# ProPrj__-__2025-12-05.net
KiCad netlist of a schematic drawn in EasyEDA Pro
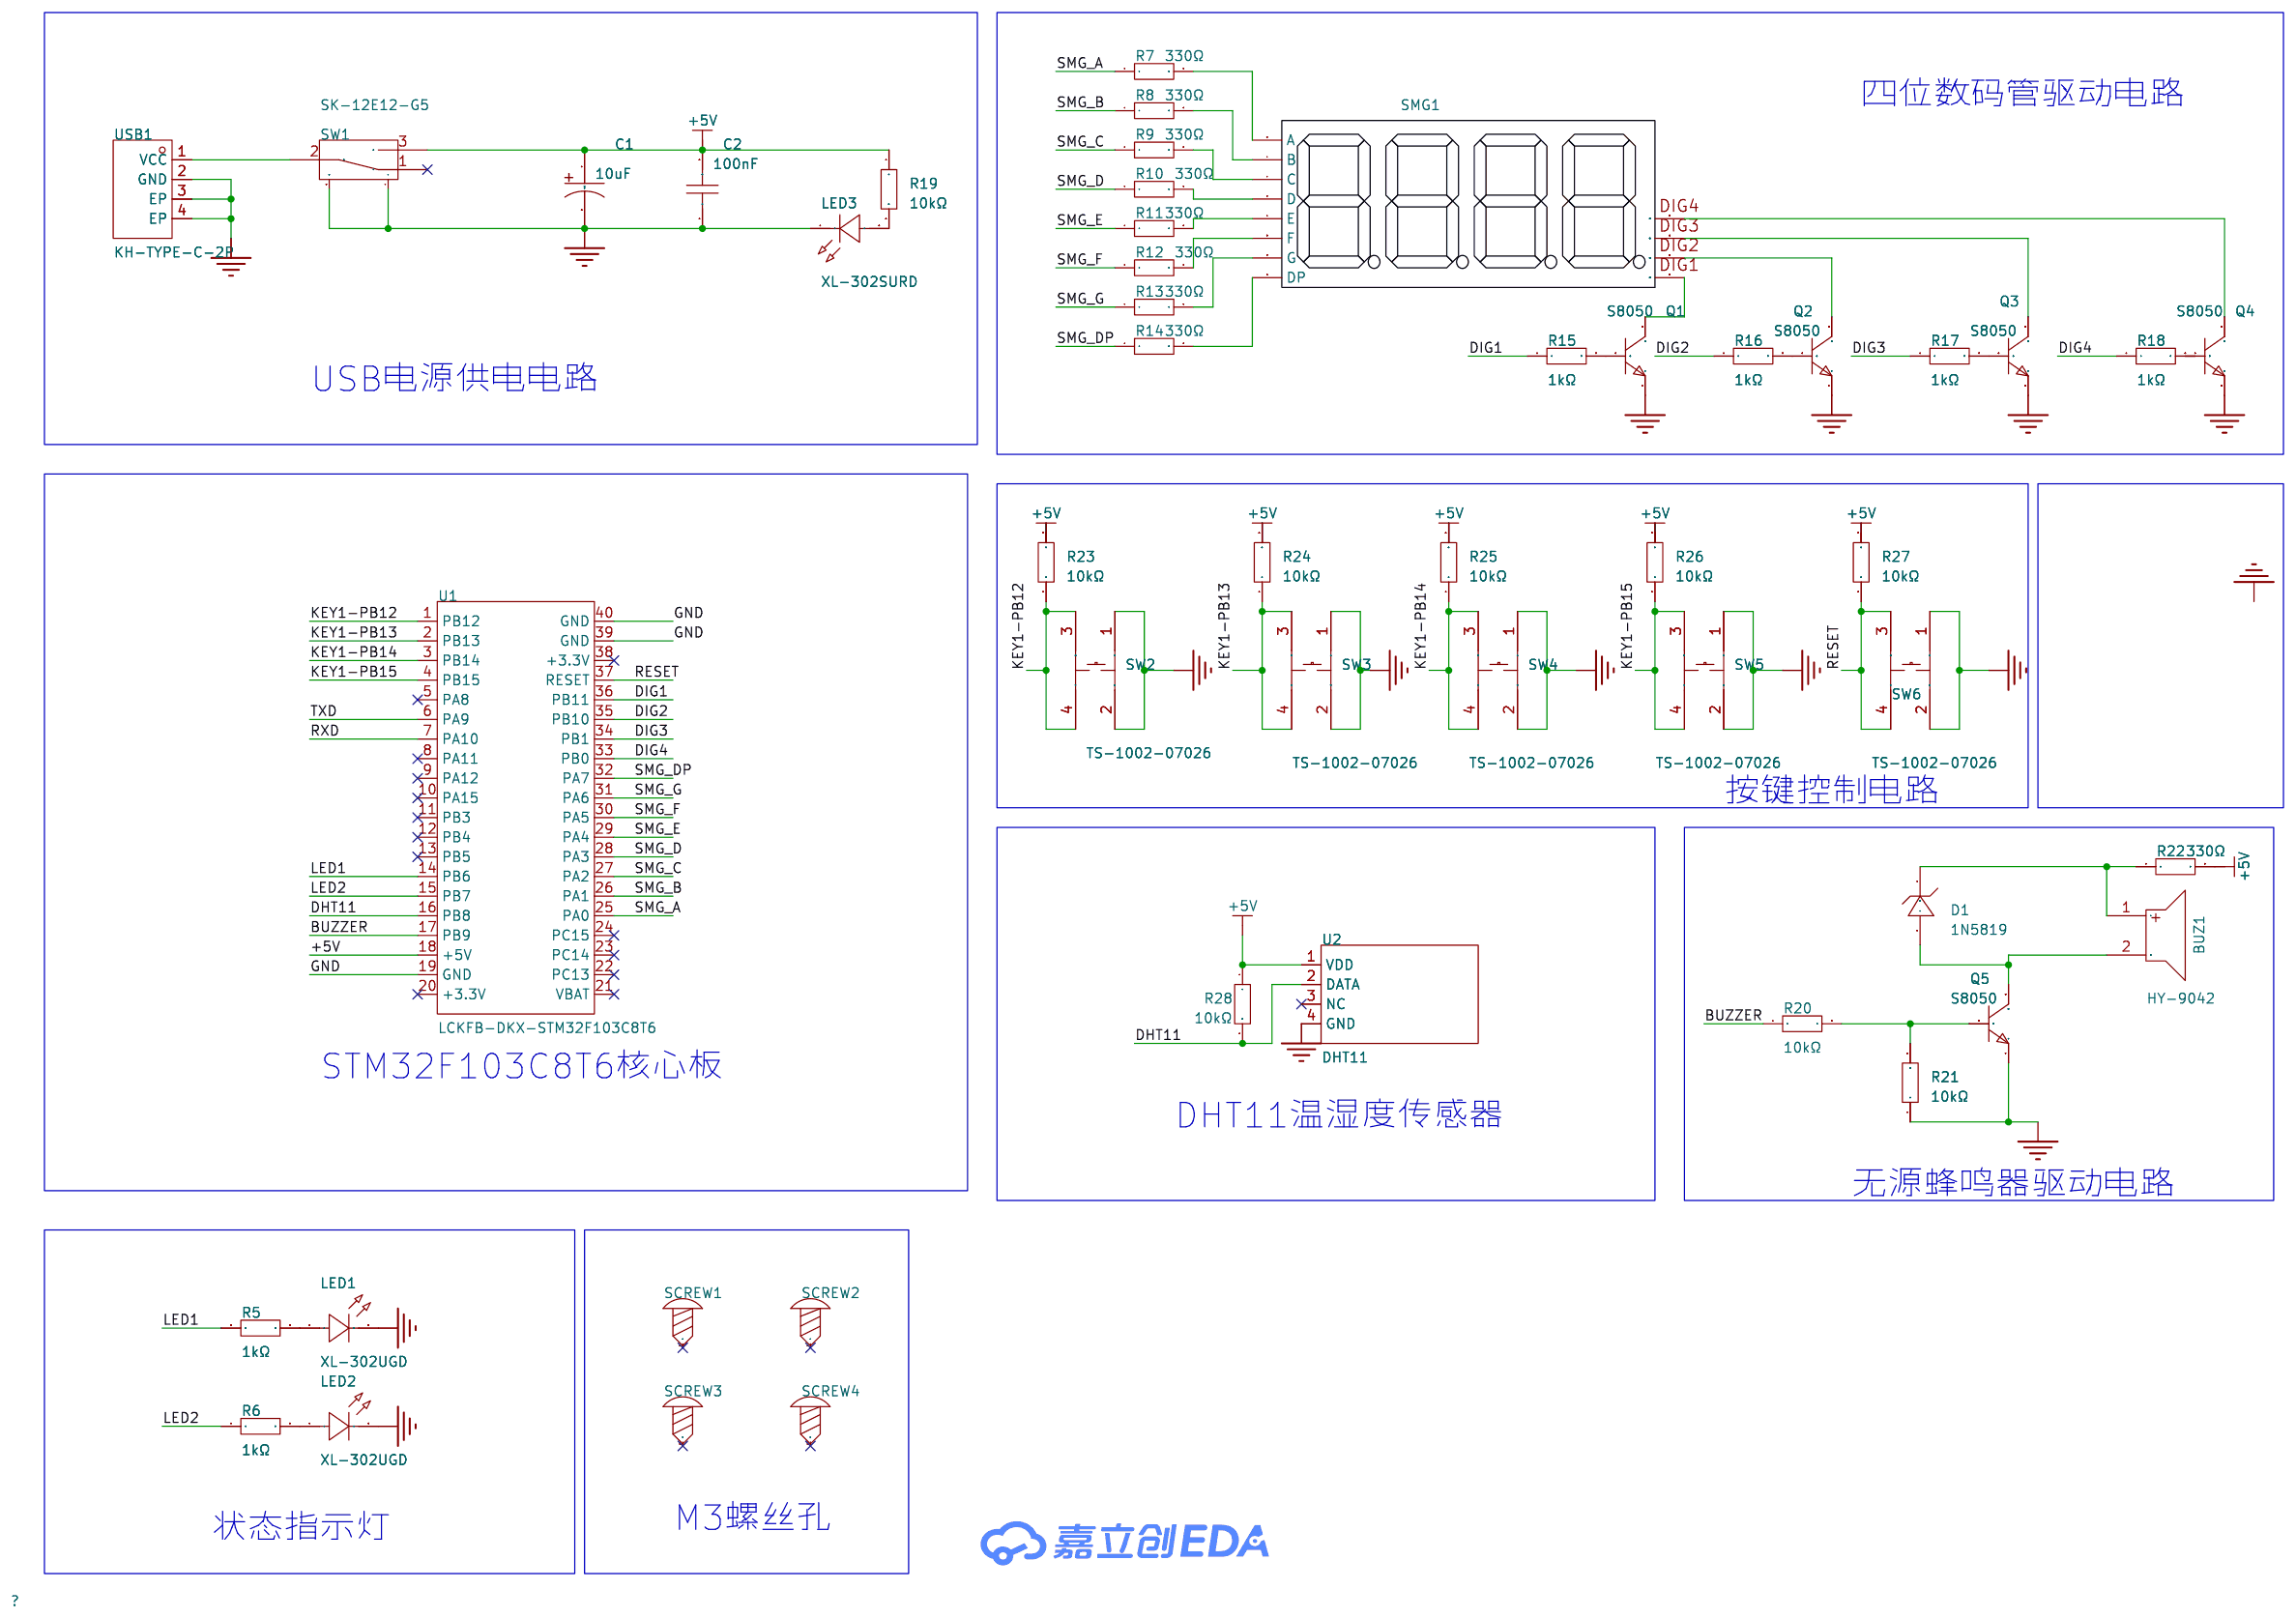
[diagram p0: schematic sheet]

(export (version "E")
  (design (tool "Eeschema 10.0.6"))
  (components
    (comp (ref "BUZ1")
      (value "HY-9042")
      (footprint "easyedapro:BUZ-TH_BD9.0-P4.00-D0.6-FD")
      (libsource (lib "easyedapro") (part "HY-9042"))
    )
    (comp (ref "C1")
      (value "10uF")
      (footprint "easyedapro:CAP-TH_BD4.0-P1.50-D0.8-FD")
      (description "容值:10uF;精度:±20%;额定电压:25V;")
      (fields
        (field (name "Manufacturer Part") "KF1E100MB050A00CV0")
        (field (name "Manufacturer") "HUAWEI(华威集团)")
      )
      (libsource (lib "easyedapro") (part "KF1E100MB050A00CV0"))
    )
    (comp (ref "C2")
      (value "100nF")
      (footprint "easyedapro:CAP-TH_L5.0-W2.5-P5.08-D0.7")
      (description "容值:100nF;精度:-20%~+80%;额定电压:50V;温度系数:Y5V;")
      (fields
        (field (name "Manufacturer Part") "CC1H104ZC74D3F5O30MN")
        (field (name "Manufacturer") "Dersonic(德尔创)")
      )
      (libsource (lib "easyedapro") (part "CC1H104ZC74D3F5O30MN"))
    )
    (comp (ref "D1")
      (value "1N5819")
      (footprint "easyedapro:DO-41_BD2.4-L4.7-P8.70-D0.9-RD")
      (description "二极管配置:独立式;正向压降(Vf):900mV@3A;直流反向耐压(Vr):40V;整流电流:1A;")
      (fields (field (name "Manufacturer") "LGE(鲁光)"))
      (libsource (lib "easyedapro") (part "1N5819_C402218"))
    )
    (comp (ref "LED1")
      (value "XL-302UGD")
      (footprint "easyedapro:LED-TH_BD3.8-P2.54-FD_GREEN")
      (fields (field (name "Manufacturer") "XINGLIGHT(成兴光)"))
      (libsource (lib "easyedapro") (part "XL-302UGD"))
    )
    (comp (ref "LED2")
      (value "XL-302UGD")
      (footprint "easyedapro:LED-TH_BD3.8-P2.54-FD_GREEN")
      (fields (field (name "Manufacturer") "XINGLIGHT(成兴光)"))
      (libsource (lib "easyedapro") (part "XL-302UGD"))
    )
    (comp (ref "LED3")
      (value "XL-302SURD")
      (footprint "easyedapro:LED-TH_BD3.8-P2.54-RD")
      (fields (field (name "Manufacturer") "XINGLIGHT(成兴光)"))
      (libsource (lib "easyedapro") (part "XL-302SURD"))
    )
    (comp (ref "Q1")
      (value "S8050")
      (footprint "easyedapro:TO-92-3_L4.5-W3.5-P1.27-L")
      (description "晶体管类型:NPN;集电极电流(Ic):500mA;集射极击穿电压(Vceo):25V;耗散功率(Pd):625mW;直流电流增益(hFE):160@50mA,1V;")
      (fields (field (name "Manufacturer") "JSMSEMI(杰盛微)"))
      (libsource (lib "easyedapro") (part "S8050_C2931492"))
    )
    (comp (ref "Q2")
      (value "S8050")
      (footprint "easyedapro:TO-92-3_L4.5-W3.5-P1.27-L")
      (description "晶体管类型:NPN;集电极电流(Ic):500mA;集射极击穿电压(Vceo):25V;耗散功率(Pd):625mW;直流电流增益(hFE):160@50mA,1V;")
      (fields (field (name "Manufacturer") "JSMSEMI(杰盛微)"))
      (libsource (lib "easyedapro") (part "S8050_C2931492"))
    )
    (comp (ref "Q3")
      (value "S8050")
      (footprint "easyedapro:TO-92-3_L4.5-W3.5-P1.27-L")
      (description "晶体管类型:NPN;集电极电流(Ic):500mA;集射极击穿电压(Vceo):25V;耗散功率(Pd):625mW;直流电流增益(hFE):160@50mA,1V;")
      (fields (field (name "Manufacturer") "JSMSEMI(杰盛微)"))
      (libsource (lib "easyedapro") (part "S8050_C2931492"))
    )
    (comp (ref "Q4")
      (value "S8050")
      (footprint "easyedapro:TO-92-3_L4.5-W3.5-P1.27-L")
      (description "晶体管类型:NPN;集电极电流(Ic):500mA;集射极击穿电压(Vceo):25V;耗散功率(Pd):625mW;直流电流增益(hFE):160@50mA,1V;")
      (fields (field (name "Manufacturer") "JSMSEMI(杰盛微)"))
      (libsource (lib "easyedapro") (part "S8050_C2931492"))
    )
    (comp (ref "Q5")
      (value "S8050")
      (footprint "easyedapro:TO-92-3_L4.5-W3.5-P1.27-L")
      (description "晶体管类型:NPN;集电极电流(Ic):500mA;集射极击穿电压(Vceo):25V;耗散功率(Pd):625mW;直流电流增益(hFE):160@50mA,1V;")
      (fields (field (name "Manufacturer") "JSMSEMI(杰盛微)"))
      (libsource (lib "easyedapro") (part "S8050_C2931492"))
    )
    (comp (ref "R5")
      (value "1kΩ")
      (footprint "easyedapro:RES-TH_BD2.2-L6.5-P10.50-D0.6")
      (description "电阻类型:金属膜电阻;阻值:1kΩ;精度:±5%;功率:250mW;")
      (fields (field (name "Manufacturer Part") "MFR-25JT-52-1K") (field (name "Manufacturer") "YAGEO(国巨)"))
      (libsource (lib "easyedapro") (part "MFR-25JT-52-1K"))
    )
    (comp (ref "R6")
      (value "1kΩ")
      (footprint "easyedapro:RES-TH_BD2.2-L6.5-P10.50-D0.6")
      (description "电阻类型:金属膜电阻;阻值:1kΩ;精度:±5%;功率:250mW;")
      (fields (field (name "Manufacturer Part") "MFR-25JT-52-1K") (field (name "Manufacturer") "YAGEO(国巨)"))
      (libsource (lib "easyedapro") (part "MFR-25JT-52-1K"))
    )
    (comp (ref "R7")
      (value "330Ω")
      (footprint "easyedapro:RES-TH_BD2.2-L6.5-P10.50-D0.6")
      (description "电阻类型:金属膜电阻;阻值:330Ω;精度:±1%;功率:250mW;温度系数:±50ppm/°C;")
      (fields (field (name "Manufacturer Part") "MFR-25FTE52-330R") (field (name "Manufacturer") "YAGEO(国巨)"))
      (libsource (lib "easyedapro") (part "MFR-25FTE52-330R"))
    )
    (comp (ref "R8")
      (value "330Ω")
      (footprint "easyedapro:RES-TH_BD2.2-L6.5-P10.50-D0.6")
      (description "电阻类型:金属膜电阻;阻值:330Ω;精度:±1%;功率:250mW;温度系数:±50ppm/°C;")
      (fields (field (name "Manufacturer Part") "MFR-25FTE52-330R") (field (name "Manufacturer") "YAGEO(国巨)"))
      (libsource (lib "easyedapro") (part "MFR-25FTE52-330R"))
    )
    (comp (ref "R9")
      (value "330Ω")
      (footprint "easyedapro:RES-TH_BD2.2-L6.5-P10.50-D0.6")
      (description "电阻类型:金属膜电阻;阻值:330Ω;精度:±1%;功率:250mW;温度系数:±50ppm/°C;")
      (fields (field (name "Manufacturer Part") "MFR-25FTE52-330R") (field (name "Manufacturer") "YAGEO(国巨)"))
      (libsource (lib "easyedapro") (part "MFR-25FTE52-330R"))
    )
    (comp (ref "R10")
      (value "330Ω")
      (footprint "easyedapro:RES-TH_BD2.2-L6.5-P10.50-D0.6")
      (description "电阻类型:金属膜电阻;阻值:330Ω;精度:±1%;功率:250mW;温度系数:±50ppm/°C;")
      (fields (field (name "Manufacturer Part") "MFR-25FTE52-330R") (field (name "Manufacturer") "YAGEO(国巨)"))
      (libsource (lib "easyedapro") (part "MFR-25FTE52-330R"))
    )
    (comp (ref "R11")
      (value "330Ω")
      (footprint "easyedapro:RES-TH_BD2.2-L6.5-P10.50-D0.6")
      (description "电阻类型:金属膜电阻;阻值:330Ω;精度:±1%;功率:250mW;温度系数:±50ppm/°C;")
      (fields (field (name "Manufacturer Part") "MFR-25FTE52-330R") (field (name "Manufacturer") "YAGEO(国巨)"))
      (libsource (lib "easyedapro") (part "MFR-25FTE52-330R"))
    )
    (comp (ref "R12")
      (value "330Ω")
      (footprint "easyedapro:RES-TH_BD2.2-L6.5-P10.50-D0.6")
      (description "电阻类型:金属膜电阻;阻值:330Ω;精度:±1%;功率:250mW;温度系数:±50ppm/°C;")
      (fields (field (name "Manufacturer Part") "MFR-25FTE52-330R") (field (name "Manufacturer") "YAGEO(国巨)"))
      (libsource (lib "easyedapro") (part "MFR-25FTE52-330R"))
    )
    (comp (ref "R13")
      (value "330Ω")
      (footprint "easyedapro:RES-TH_BD2.2-L6.5-P10.50-D0.6")
      (description "电阻类型:金属膜电阻;阻值:330Ω;精度:±1%;功率:250mW;温度系数:±50ppm/°C;")
      (fields (field (name "Manufacturer Part") "MFR-25FTE52-330R") (field (name "Manufacturer") "YAGEO(国巨)"))
      (libsource (lib "easyedapro") (part "MFR-25FTE52-330R"))
    )
    (comp (ref "R14")
      (value "330Ω")
      (footprint "easyedapro:RES-TH_BD2.2-L6.5-P10.50-D0.6")
      (description "电阻类型:金属膜电阻;阻值:330Ω;精度:±1%;功率:250mW;温度系数:±50ppm/°C;")
      (fields (field (name "Manufacturer Part") "MFR-25FTE52-330R") (field (name "Manufacturer") "YAGEO(国巨)"))
      (libsource (lib "easyedapro") (part "MFR-25FTE52-330R"))
    )
    (comp (ref "R15")
      (value "1kΩ")
      (footprint "easyedapro:RES-TH_BD2.2-L6.5-P10.50-D0.6")
      (description "电阻类型:金属膜电阻;阻值:1kΩ;精度:±5%;功率:250mW;")
      (fields (field (name "Manufacturer Part") "MFR-25JT-52-1K") (field (name "Manufacturer") "YAGEO(国巨)"))
      (libsource (lib "easyedapro") (part "MFR-25JT-52-1K"))
    )
    (comp (ref "R16")
      (value "1kΩ")
      (footprint "easyedapro:RES-TH_BD2.2-L6.5-P10.50-D0.6")
      (description "电阻类型:金属膜电阻;阻值:1kΩ;精度:±5%;功率:250mW;")
      (fields (field (name "Manufacturer Part") "MFR-25JT-52-1K") (field (name "Manufacturer") "YAGEO(国巨)"))
      (libsource (lib "easyedapro") (part "MFR-25JT-52-1K"))
    )
    (comp (ref "R17")
      (value "1kΩ")
      (footprint "easyedapro:RES-TH_BD2.2-L6.5-P10.50-D0.6")
      (description "电阻类型:金属膜电阻;阻值:1kΩ;精度:±5%;功率:250mW;")
      (fields (field (name "Manufacturer Part") "MFR-25JT-52-1K") (field (name "Manufacturer") "YAGEO(国巨)"))
      (libsource (lib "easyedapro") (part "MFR-25JT-52-1K"))
    )
    (comp (ref "R18")
      (value "1kΩ")
      (footprint "easyedapro:RES-TH_BD2.2-L6.5-P10.50-D0.6")
      (description "电阻类型:金属膜电阻;阻值:1kΩ;精度:±5%;功率:250mW;")
      (fields (field (name "Manufacturer Part") "MFR-25JT-52-1K") (field (name "Manufacturer") "YAGEO(国巨)"))
      (libsource (lib "easyedapro") (part "MFR-25JT-52-1K"))
    )
    (comp (ref "R19")
      (value "10kΩ")
      (footprint "easyedapro:RES-TH_BD2.4-L6.3-P10.30-D0.6")
      (description "电阻类型:金属膜电阻;阻值:10kΩ;精度:±5%;功率:250mW;")
      (fields (field (name "Manufacturer Part") "MFR-25JT-52-10K") (field (name "Manufacturer") "YAGEO(国巨)"))
      (libsource (lib "easyedapro") (part "MFR-25JT-52-10K"))
    )
    (comp (ref "R20")
      (value "10kΩ")
      (footprint "easyedapro:RES-TH_BD2.4-L6.3-P10.30-D0.6")
      (description "电阻类型:金属膜电阻;阻值:10kΩ;精度:±5%;功率:250mW;")
      (fields (field (name "Manufacturer Part") "MFR-25JT-52-10K") (field (name "Manufacturer") "YAGEO(国巨)"))
      (libsource (lib "easyedapro") (part "MFR-25JT-52-10K"))
    )
    (comp (ref "R21")
      (value "10kΩ")
      (footprint "easyedapro:RES-TH_BD2.4-L6.3-P10.30-D0.6")
      (description "电阻类型:金属膜电阻;阻值:10kΩ;精度:±5%;功率:250mW;")
      (fields (field (name "Manufacturer Part") "MFR-25JT-52-10K") (field (name "Manufacturer") "YAGEO(国巨)"))
      (libsource (lib "easyedapro") (part "MFR-25JT-52-10K"))
    )
    (comp (ref "R22")
      (value "330Ω")
      (footprint "easyedapro:RES-TH_BD2.2-L6.5-P10.50-D0.6")
      (description "电阻类型:金属膜电阻;阻值:330Ω;精度:±1%;功率:250mW;温度系数:±50ppm/°C;")
      (fields (field (name "Manufacturer Part") "MFR-25FTE52-330R") (field (name "Manufacturer") "YAGEO(国巨)"))
      (libsource (lib "easyedapro") (part "MFR-25FTE52-330R"))
    )
    (comp (ref "R23")
      (value "10kΩ")
      (footprint "easyedapro:RES-TH_BD2.4-L6.3-P10.30-D0.6")
      (description "电阻类型:金属膜电阻;阻值:10kΩ;精度:±5%;功率:250mW;")
      (fields (field (name "Manufacturer Part") "MFR-25JT-52-10K") (field (name "Manufacturer") "YAGEO(国巨)"))
      (libsource (lib "easyedapro") (part "MFR-25JT-52-10K"))
    )
    (comp (ref "R24")
      (value "10kΩ")
      (footprint "easyedapro:RES-TH_BD2.4-L6.3-P10.30-D0.6")
      (description "电阻类型:金属膜电阻;阻值:10kΩ;精度:±5%;功率:250mW;")
      (fields (field (name "Manufacturer Part") "MFR-25JT-52-10K") (field (name "Manufacturer") "YAGEO(国巨)"))
      (libsource (lib "easyedapro") (part "MFR-25JT-52-10K"))
    )
    (comp (ref "R25")
      (value "10kΩ")
      (footprint "easyedapro:RES-TH_BD2.4-L6.3-P10.30-D0.6")
      (description "电阻类型:金属膜电阻;阻值:10kΩ;精度:±5%;功率:250mW;")
      (fields (field (name "Manufacturer Part") "MFR-25JT-52-10K") (field (name "Manufacturer") "YAGEO(国巨)"))
      (libsource (lib "easyedapro") (part "MFR-25JT-52-10K"))
    )
    (comp (ref "R26")
      (value "10kΩ")
      (footprint "easyedapro:RES-TH_BD2.4-L6.3-P10.30-D0.6")
      (description "电阻类型:金属膜电阻;阻值:10kΩ;精度:±5%;功率:250mW;")
      (fields (field (name "Manufacturer Part") "MFR-25JT-52-10K") (field (name "Manufacturer") "YAGEO(国巨)"))
      (libsource (lib "easyedapro") (part "MFR-25JT-52-10K"))
    )
    (comp (ref "R27")
      (value "10kΩ")
      (footprint "easyedapro:RES-TH_BD2.4-L6.3-P10.30-D0.6")
      (description "电阻类型:金属膜电阻;阻值:10kΩ;精度:±5%;功率:250mW;")
      (fields (field (name "Manufacturer Part") "MFR-25JT-52-10K") (field (name "Manufacturer") "YAGEO(国巨)"))
      (libsource (lib "easyedapro") (part "MFR-25JT-52-10K"))
    )
    (comp (ref "R28")
      (value "10kΩ")
      (footprint "easyedapro:RES-TH_BD2.4-L6.3-P10.30-D0.6")
      (description "电阻类型:金属膜电阻;阻值:10kΩ;精度:±5%;功率:250mW;")
      (fields (field (name "Manufacturer Part") "MFR-25JT-52-10K") (field (name "Manufacturer") "YAGEO(国巨)"))
      (libsource (lib "easyedapro") (part "MFR-25JT-52-10K"))
    )
    (comp (ref "SCREW1")
      (value "~")
      (footprint "easyedapro:M3螺丝")
      (libsource (lib "easyedapro") (part "螺丝孔"))
    )
    (comp (ref "SCREW2")
      (value "~")
      (footprint "easyedapro:M3螺丝")
      (libsource (lib "easyedapro") (part "螺丝孔"))
    )
    (comp (ref "SCREW3")
      (value "~")
      (footprint "easyedapro:M3螺丝")
      (libsource (lib "easyedapro") (part "螺丝孔"))
    )
    (comp (ref "SCREW4")
      (value "~")
      (footprint "easyedapro:M3螺丝")
      (libsource (lib "easyedapro") (part "螺丝孔"))
    )
    (comp (ref "SMG1")
      (value "~")
      (footprint "easyedapro:LED-SEG-TH_FJ5461AH")
      (libsource (lib "easyedapro") (part "LED_SEG_TH_0.56x4"))
    )
    (comp (ref "SW1")
      (value "SK-12E12-G5")
      (footprint "easyedapro:SW-TH_SK-12E12-G5")
      (description "电路结构:单刀双掷;安装方式:-;额定电流:-;额定电压:-;工作寿命:5千次;")
      (fields (field (name "Manufacturer") "韩国韩荣"))
      (libsource (lib "easyedapro") (part "SK-12E12-G5"))
    )
    (comp (ref "SW2")
      (value "TS-1002-07026")
      (footprint "easyedapro:SW-TH_4P-L6.0-W6.0-P4.50-LS6.5")
      (description "电路结构:单刀单掷;按钮形状:圆形按钮;安装方式:直插;开关长度:6mm;开关宽度:6mm;开关高度:7mm;触点电流:50mA;额定电压:12V;带灯:-;工作寿命:-;")
      (fields (field (name "Manufacturer") "XUNPU(讯普)"))
      (libsource (lib "easyedapro") (part "TS-1002-07026"))
    )
    (comp (ref "SW3")
      (value "TS-1002-07026")
      (footprint "easyedapro:SW-TH_4P-L6.0-W6.0-P4.50-LS6.5")
      (description "电路结构:单刀单掷;按钮形状:圆形按钮;安装方式:直插;开关长度:6mm;开关宽度:6mm;开关高度:7mm;触点电流:50mA;额定电压:12V;带灯:-;工作寿命:-;")
      (fields (field (name "Manufacturer") "XUNPU(讯普)"))
      (libsource (lib "easyedapro") (part "TS-1002-07026"))
    )
    (comp (ref "SW4")
      (value "TS-1002-07026")
      (footprint "easyedapro:SW-TH_4P-L6.0-W6.0-P4.50-LS6.5")
      (description "电路结构:单刀单掷;按钮形状:圆形按钮;安装方式:直插;开关长度:6mm;开关宽度:6mm;开关高度:7mm;触点电流:50mA;额定电压:12V;带灯:-;工作寿命:-;")
      (fields (field (name "Manufacturer") "XUNPU(讯普)"))
      (libsource (lib "easyedapro") (part "TS-1002-07026"))
    )
    (comp (ref "SW5")
      (value "TS-1002-07026")
      (footprint "easyedapro:SW-TH_4P-L6.0-W6.0-P4.50-LS6.5")
      (description "电路结构:单刀单掷;按钮形状:圆形按钮;安装方式:直插;开关长度:6mm;开关宽度:6mm;开关高度:7mm;触点电流:50mA;额定电压:12V;带灯:-;工作寿命:-;")
      (fields (field (name "Manufacturer") "XUNPU(讯普)"))
      (libsource (lib "easyedapro") (part "TS-1002-07026"))
    )
    (comp (ref "SW6")
      (value "TS-1002-07026")
      (footprint "easyedapro:SW-TH_4P-L6.0-W6.0-P4.50-LS6.5")
      (description "电路结构:单刀单掷;按钮形状:圆形按钮;安装方式:直插;开关长度:6mm;开关宽度:6mm;开关高度:7mm;触点电流:50mA;额定电压:12V;带灯:-;工作寿命:-;")
      (fields (field (name "Manufacturer") "XUNPU(讯普)"))
      (libsource (lib "easyedapro") (part "TS-1002-07026"))
    )
    (comp (ref "U1")
      (value "LCKFB-DKX-STM32F103C8T6")
      (footprint "easyedapro:CONN-TH_L53.3-W22.9_STM32F103C8T6-CARD")
      (fields (field (name "Manufacturer") "立创开发板"))
      (libsource (lib "easyedapro") (part "LCKFB-DKX-STM32F103C8T6"))
    )
    (comp (ref "U2")
      (value "DHT11")
      (footprint "easyedapro:SENSOR-TH_DHT11")
      (description "新款电容式数字温湿度传感器,老款已停产16.1x12.6x5.8mm")
      (fields (field (name "Manufacturer") "广州奥松"))
      (libsource (lib "easyedapro") (part "DHT11"))
    )
    (comp (ref "USB1")
      (value "KH-TYPE-C-2P")
      (footprint "easyedapro:USB-SMD_KH-TYPE-C-2P")
      (description "连接器类型:Type-C;协议标准:-;公母:-;安装方式:-;触点数量:2P;端口数量:-;额定电流 - 电源:-;工作温度:-;")
      (fields (field (name "Manufacturer") "kinghelm(金航标)"))
      (libsource (lib "easyedapro") (part "KH-TYPE-C-2P"))
    )
  )
  (nets
    (net (code "1") (name "+5V") (class "Default")
      (node (ref "C1") (pin "1") (pinfunction "1_1") (pintype "unspecified"))
      (node (ref "C2") (pin "2") (pinfunction "2_2") (pintype "unspecified"))
      (node (ref "R19") (pin "1") (pinfunction "1_1") (pintype "unspecified"))
      (node (ref "R22") (pin "2") (pinfunction "2_2") (pintype "input"))
      (node (ref "R23") (pin "2") (pinfunction "2_2") (pintype "unspecified"))
      (node (ref "R24") (pin "2") (pinfunction "2_2") (pintype "unspecified"))
      (node (ref "R25") (pin "2") (pinfunction "2_2") (pintype "unspecified"))
      (node (ref "R26") (pin "2") (pinfunction "2_2") (pintype "unspecified"))
      (node (ref "R27") (pin "2") (pinfunction "2_2") (pintype "unspecified"))
      (node (ref "R28") (pin "1") (pinfunction "1_1") (pintype "unspecified"))
      (node (ref "SW1") (pin "3") (pinfunction "3_3") (pintype "unspecified"))
      (node (ref "U1") (pin "18") (pinfunction "+5V_18") (pintype "unspecified"))
      (node (ref "U2") (pin "1") (pinfunction "VDD_1") (pintype "unspecified"))
    )
    (net (code "2") (name "/BUZZER") (class "Default")
      (node (ref "R20") (pin "1") (pinfunction "1_1") (pintype "unspecified"))
      (node (ref "U1") (pin "17") (pinfunction "PB9_17") (pintype "unspecified"))
    )
    (net (code "3") (name "/DHT11") (class "Default")
      (node (ref "R28") (pin "2") (pinfunction "2_2") (pintype "unspecified"))
      (node (ref "U1") (pin "16") (pinfunction "PB8_16") (pintype "unspecified"))
      (node (ref "U2") (pin "2") (pinfunction "DATA_2") (pintype "unspecified"))
    )
    (net (code "4") (name "/DIG1") (class "Default")
      (node (ref "R15") (pin "1") (pinfunction "1_1") (pintype "unspecified"))
      (node (ref "U1") (pin "36") (pinfunction "PB11_36") (pintype "unspecified"))
    )
    (net (code "5") (name "/DIG2") (class "Default")
      (node (ref "R16") (pin "1") (pinfunction "1_1") (pintype "unspecified"))
      (node (ref "U1") (pin "35") (pinfunction "PB10_35") (pintype "unspecified"))
    )
    (net (code "6") (name "/DIG3") (class "Default")
      (node (ref "R17") (pin "1") (pinfunction "1_1") (pintype "unspecified"))
      (node (ref "U1") (pin "34") (pinfunction "PB1_34") (pintype "unspecified"))
    )
    (net (code "7") (name "/DIG4") (class "Default")
      (node (ref "R18") (pin "1") (pinfunction "1_1") (pintype "unspecified"))
      (node (ref "U1") (pin "33") (pinfunction "PB0_33") (pintype "unspecified"))
    )
    (net (code "8") (name "/KEY1-PB12") (class "Default")
      (node (ref "R23") (pin "1") (pinfunction "1_1") (pintype "unspecified"))
      (node (ref "SW2") (pin "3") (pinfunction "3_3") (pintype "unspecified"))
      (node (ref "SW2") (pin "4") (pinfunction "4_4") (pintype "unspecified"))
      (node (ref "U1") (pin "1") (pinfunction "PB12_1") (pintype "unspecified"))
    )
    (net (code "9") (name "/KEY1-PB13") (class "Default")
      (node (ref "R24") (pin "1") (pinfunction "1_1") (pintype "unspecified"))
      (node (ref "SW3") (pin "3") (pinfunction "3_3") (pintype "unspecified"))
      (node (ref "SW3") (pin "4") (pinfunction "4_4") (pintype "unspecified"))
      (node (ref "U1") (pin "2") (pinfunction "PB13_2") (pintype "unspecified"))
    )
    (net (code "10") (name "/KEY1-PB14") (class "Default")
      (node (ref "R25") (pin "1") (pinfunction "1_1") (pintype "unspecified"))
      (node (ref "SW4") (pin "3") (pinfunction "3_3") (pintype "unspecified"))
      (node (ref "SW4") (pin "4") (pinfunction "4_4") (pintype "unspecified"))
      (node (ref "U1") (pin "3") (pinfunction "PB14_3") (pintype "unspecified"))
    )
    (net (code "11") (name "/KEY1-PB15") (class "Default")
      (node (ref "R26") (pin "1") (pinfunction "1_1") (pintype "unspecified"))
      (node (ref "SW5") (pin "3") (pinfunction "3_3") (pintype "unspecified"))
      (node (ref "SW5") (pin "4") (pinfunction "4_4") (pintype "unspecified"))
      (node (ref "U1") (pin "4") (pinfunction "PB15_4") (pintype "unspecified"))
    )
    (net (code "12") (name "/LED1") (class "Default")
      (node (ref "R5") (pin "1") (pinfunction "1_1") (pintype "unspecified"))
      (node (ref "U1") (pin "14") (pinfunction "PB6_14") (pintype "unspecified"))
    )
    (net (code "13") (name "/LED2") (class "Default")
      (node (ref "R6") (pin "1") (pinfunction "1_1") (pintype "unspecified"))
      (node (ref "U1") (pin "15") (pinfunction "PB7_15") (pintype "unspecified"))
    )
    (net (code "14") (name "/RESET") (class "Default")
      (node (ref "R27") (pin "1") (pinfunction "1_1") (pintype "unspecified"))
      (node (ref "SW6") (pin "3") (pinfunction "3_3") (pintype "unspecified"))
      (node (ref "SW6") (pin "4") (pinfunction "4_4") (pintype "unspecified"))
      (node (ref "U1") (pin "37") (pinfunction "RESET_37") (pintype "unspecified"))
    )
    (net (code "15") (name "/RXD") (class "Default")
      (node (ref "U1") (pin "7") (pinfunction "PA10_7") (pintype "unspecified"))
    )
    (net (code "16") (name "/SMG_A") (class "Default")
      (node (ref "R7") (pin "1") (pinfunction "1_1") (pintype "input"))
      (node (ref "U1") (pin "25") (pinfunction "PA0_25") (pintype "unspecified"))
    )
    (net (code "17") (name "/SMG_B") (class "Default")
      (node (ref "R8") (pin "1") (pinfunction "1_1") (pintype "input"))
      (node (ref "U1") (pin "26") (pinfunction "PA1_26") (pintype "unspecified"))
    )
    (net (code "18") (name "/SMG_C") (class "Default")
      (node (ref "R9") (pin "1") (pinfunction "1_1") (pintype "input"))
      (node (ref "U1") (pin "27") (pinfunction "PA2_27") (pintype "unspecified"))
    )
    (net (code "19") (name "/SMG_D") (class "Default")
      (node (ref "R10") (pin "1") (pinfunction "1_1") (pintype "input"))
      (node (ref "U1") (pin "28") (pinfunction "PA3_28") (pintype "unspecified"))
    )
    (net (code "20") (name "/SMG_DP") (class "Default")
      (node (ref "R14") (pin "1") (pinfunction "1_1") (pintype "input"))
      (node (ref "U1") (pin "32") (pinfunction "PA7_32") (pintype "unspecified"))
    )
    (net (code "21") (name "/SMG_E") (class "Default")
      (node (ref "R11") (pin "1") (pinfunction "1_1") (pintype "input"))
      (node (ref "U1") (pin "29") (pinfunction "PA4_29") (pintype "unspecified"))
    )
    (net (code "22") (name "/SMG_F") (class "Default")
      (node (ref "R12") (pin "1") (pinfunction "1_1") (pintype "input"))
      (node (ref "U1") (pin "30") (pinfunction "PA5_30") (pintype "unspecified"))
    )
    (net (code "23") (name "/SMG_G") (class "Default")
      (node (ref "R13") (pin "1") (pinfunction "1_1") (pintype "input"))
      (node (ref "U1") (pin "31") (pinfunction "PA6_31") (pintype "unspecified"))
    )
    (net (code "24") (name "/TXD") (class "Default")
      (node (ref "U1") (pin "6") (pinfunction "PA9_6") (pintype "unspecified"))
    )
    (net (code "25") (name "GND") (class "Default")
      (node (ref "C1") (pin "2") (pinfunction "2_2") (pintype "unspecified"))
      (node (ref "C2") (pin "1") (pinfunction "1_1") (pintype "unspecified"))
      (node (ref "LED1") (pin "2") (pinfunction "K_2") (pintype "unspecified"))
      (node (ref "LED2") (pin "2") (pinfunction "K_2") (pintype "unspecified"))
      (node (ref "LED3") (pin "1") (pinfunction "K_1") (pintype "unspecified"))
      (node (ref "Q1") (pin "1") (pinfunction "E_1") (pintype "unspecified"))
      (node (ref "Q2") (pin "1") (pinfunction "E_1") (pintype "unspecified"))
      (node (ref "Q3") (pin "1") (pinfunction "E_1") (pintype "unspecified"))
      (node (ref "Q4") (pin "1") (pinfunction "E_1") (pintype "unspecified"))
      (node (ref "Q5") (pin "1") (pinfunction "E_1") (pintype "unspecified"))
      (node (ref "R21") (pin "1") (pinfunction "1_1") (pintype "unspecified"))
      (node (ref "SW1") (pin "4") (pinfunction "4_4") (pintype "unspecified"))
      (node (ref "SW1") (pin "5") (pinfunction "5_5") (pintype "unspecified"))
      (node (ref "SW2") (pin "1") (pinfunction "1_1") (pintype "unspecified"))
      (node (ref "SW2") (pin "2") (pinfunction "2_2") (pintype "unspecified"))
      (node (ref "SW3") (pin "1") (pinfunction "1_1") (pintype "unspecified"))
      (node (ref "SW3") (pin "2") (pinfunction "2_2") (pintype "unspecified"))
      (node (ref "SW4") (pin "1") (pinfunction "1_1") (pintype "unspecified"))
      (node (ref "SW4") (pin "2") (pinfunction "2_2") (pintype "unspecified"))
      (node (ref "SW5") (pin "1") (pinfunction "1_1") (pintype "unspecified"))
      (node (ref "SW5") (pin "2") (pinfunction "2_2") (pintype "unspecified"))
      (node (ref "SW6") (pin "1") (pinfunction "1_1") (pintype "unspecified"))
      (node (ref "SW6") (pin "2") (pinfunction "2_2") (pintype "unspecified"))
      (node (ref "U1") (pin "19") (pinfunction "GND_19") (pintype "unspecified"))
      (node (ref "U1") (pin "39") (pinfunction "GND_39") (pintype "unspecified"))
      (node (ref "U1") (pin "40") (pinfunction "GND_40") (pintype "unspecified"))
      (node (ref "U2") (pin "4") (pinfunction "GND_4") (pintype "unspecified"))
      (node (ref "USB1") (pin "2") (pinfunction "GND_2") (pintype "unspecified"))
      (node (ref "USB1") (pin "3") (pinfunction "EP_3") (pintype "unspecified"))
      (node (ref "USB1") (pin "4") (pinfunction "EP_4") (pintype "unspecified"))
    )
    (net (code "26") (name "Net-(D1-A)") (class "Default")
      (node (ref "BUZ1") (pin "2") (pinfunction "2_2") (pintype "unspecified"))
      (node (ref "D1") (pin "2") (pinfunction "A_2") (pintype "unspecified"))
      (node (ref "Q5") (pin "3") (pinfunction "C_3") (pintype "unspecified"))
    )
    (net (code "27") (name "Net-(D1-C)") (class "Default")
      (node (ref "BUZ1") (pin "1") (pinfunction "1_1") (pintype "unspecified"))
      (node (ref "D1") (pin "1") (pinfunction "C_1") (pintype "unspecified"))
      (node (ref "R22") (pin "1") (pinfunction "1_1") (pintype "input"))
    )
    (net (code "28") (name "Net-(LED1-A)") (class "Default")
      (node (ref "LED1") (pin "1") (pinfunction "A_1") (pintype "unspecified"))
      (node (ref "R5") (pin "2") (pinfunction "2_2") (pintype "unspecified"))
    )
    (net (code "29") (name "Net-(LED2-A)") (class "Default")
      (node (ref "LED2") (pin "1") (pinfunction "A_1") (pintype "unspecified"))
      (node (ref "R6") (pin "2") (pinfunction "2_2") (pintype "unspecified"))
    )
    (net (code "30") (name "Net-(LED3-A)") (class "Default")
      (node (ref "LED3") (pin "2") (pinfunction "A_2") (pintype "unspecified"))
      (node (ref "R19") (pin "2") (pinfunction "2_2") (pintype "unspecified"))
    )
    (net (code "31") (name "Net-(Q1-B)") (class "Default")
      (node (ref "Q1") (pin "2") (pinfunction "B_2") (pintype "unspecified"))
      (node (ref "R15") (pin "2") (pinfunction "2_2") (pintype "unspecified"))
    )
    (net (code "32") (name "Net-(Q1-C)") (class "Default")
      (node (ref "Q1") (pin "3") (pinfunction "C_3") (pintype "unspecified"))
      (node (ref "SMG1") (pin "12") (pinfunction "DIG1_12") (pintype "input"))
    )
    (net (code "33") (name "Net-(Q2-B)") (class "Default")
      (node (ref "Q2") (pin "2") (pinfunction "B_2") (pintype "unspecified"))
      (node (ref "R16") (pin "2") (pinfunction "2_2") (pintype "unspecified"))
    )
    (net (code "34") (name "Net-(Q2-C)") (class "Default")
      (node (ref "Q2") (pin "3") (pinfunction "C_3") (pintype "unspecified"))
      (node (ref "SMG1") (pin "9") (pinfunction "DIG2_9") (pintype "input"))
    )
    (net (code "35") (name "Net-(Q3-B)") (class "Default")
      (node (ref "Q3") (pin "2") (pinfunction "B_2") (pintype "unspecified"))
      (node (ref "R17") (pin "2") (pinfunction "2_2") (pintype "unspecified"))
    )
    (net (code "36") (name "Net-(Q3-C)") (class "Default")
      (node (ref "Q3") (pin "3") (pinfunction "C_3") (pintype "unspecified"))
      (node (ref "SMG1") (pin "8") (pinfunction "DIG3_8") (pintype "input"))
    )
    (net (code "37") (name "Net-(Q4-B)") (class "Default")
      (node (ref "Q4") (pin "2") (pinfunction "B_2") (pintype "unspecified"))
      (node (ref "R18") (pin "2") (pinfunction "2_2") (pintype "unspecified"))
    )
    (net (code "38") (name "Net-(Q4-C)") (class "Default")
      (node (ref "Q4") (pin "3") (pinfunction "C_3") (pintype "unspecified"))
      (node (ref "SMG1") (pin "6") (pinfunction "DIG4_6") (pintype "input"))
    )
    (net (code "39") (name "Net-(Q5-B)") (class "Default")
      (node (ref "Q5") (pin "2") (pinfunction "B_2") (pintype "unspecified"))
      (node (ref "R20") (pin "2") (pinfunction "2_2") (pintype "unspecified"))
      (node (ref "R21") (pin "2") (pinfunction "2_2") (pintype "unspecified"))
    )
    (net (code "40") (name "Net-(SMG1-A)") (class "Default")
      (node (ref "R7") (pin "2") (pinfunction "2_2") (pintype "input"))
      (node (ref "SMG1") (pin "11") (pinfunction "A_11") (pintype "input"))
    )
    (net (code "41") (name "Net-(SMG1-B)") (class "Default")
      (node (ref "R8") (pin "2") (pinfunction "2_2") (pintype "input"))
      (node (ref "SMG1") (pin "7") (pinfunction "B_7") (pintype "input"))
    )
    (net (code "42") (name "Net-(SMG1-C)") (class "Default")
      (node (ref "R9") (pin "2") (pinfunction "2_2") (pintype "input"))
      (node (ref "SMG1") (pin "4") (pinfunction "C_4") (pintype "input"))
    )
    (net (code "43") (name "Net-(SMG1-D)") (class "Default")
      (node (ref "R10") (pin "2") (pinfunction "2_2") (pintype "input"))
      (node (ref "SMG1") (pin "2") (pinfunction "D_2") (pintype "input"))
    )
    (net (code "44") (name "Net-(SMG1-DP)") (class "Default")
      (node (ref "R14") (pin "2") (pinfunction "2_2") (pintype "input"))
      (node (ref "SMG1") (pin "3") (pinfunction "DP_3") (pintype "input"))
    )
    (net (code "45") (name "Net-(SMG1-E)") (class "Default")
      (node (ref "R11") (pin "2") (pinfunction "2_2") (pintype "input"))
      (node (ref "SMG1") (pin "1") (pinfunction "E_1") (pintype "input"))
    )
    (net (code "46") (name "Net-(SMG1-F)") (class "Default")
      (node (ref "R12") (pin "2") (pinfunction "2_2") (pintype "input"))
      (node (ref "SMG1") (pin "10") (pinfunction "F_10") (pintype "input"))
    )
    (net (code "47") (name "Net-(SMG1-G)") (class "Default")
      (node (ref "R13") (pin "2") (pinfunction "2_2") (pintype "input"))
      (node (ref "SMG1") (pin "5") (pinfunction "G_5") (pintype "input"))
    )
    (net (code "48") (name "Net-(USB1-VCC)") (class "Default")
      (node (ref "SW1") (pin "2") (pinfunction "2_2") (pintype "unspecified"))
      (node (ref "USB1") (pin "1") (pinfunction "VCC_1") (pintype "unspecified"))
    )
    (net (code "49") (name "unconnected-(SCREW1-Pad1)") (class "Default")
      (node (ref "SCREW1") (pin "1") (pinfunction "1_1") (pintype "input+no_connect"))
    )
    (net (code "50") (name "unconnected-(SCREW2-Pad1)") (class "Default")
      (node (ref "SCREW2") (pin "1") (pinfunction "1_1") (pintype "input+no_connect"))
    )
    (net (code "51") (name "unconnected-(SCREW3-Pad1)") (class "Default")
      (node (ref "SCREW3") (pin "1") (pinfunction "1_1") (pintype "input+no_connect"))
    )
    (net (code "52") (name "unconnected-(SCREW4-Pad1)") (class "Default")
      (node (ref "SCREW4") (pin "1") (pinfunction "1_1") (pintype "input+no_connect"))
    )
    (net (code "53") (name "unconnected-(SW1-Pad1)") (class "Default")
      (node (ref "SW1") (pin "1") (pinfunction "1_1") (pintype "unspecified+no_connect"))
    )
    (net (code "54") (name "unconnected-(U1-+3.3V-Pad20)") (class "Default")
      (node (ref "U1") (pin "20") (pinfunction "+3.3V_20") (pintype "unspecified+no_connect"))
    )
    (net (code "55") (name "unconnected-(U1-+3.3V-Pad38)") (class "Default")
      (node (ref "U1") (pin "38") (pinfunction "+3.3V_38") (pintype "unspecified+no_connect"))
    )
    (net (code "56") (name "unconnected-(U1-PA8-Pad5)") (class "Default")
      (node (ref "U1") (pin "5") (pinfunction "PA8_5") (pintype "unspecified+no_connect"))
    )
    (net (code "57") (name "unconnected-(U1-PA11-Pad8)") (class "Default")
      (node (ref "U1") (pin "8") (pinfunction "PA11_8") (pintype "unspecified+no_connect"))
    )
    (net (code "58") (name "unconnected-(U1-PA12-Pad9)") (class "Default")
      (node (ref "U1") (pin "9") (pinfunction "PA12_9") (pintype "unspecified+no_connect"))
    )
    (net (code "59") (name "unconnected-(U1-PA15-Pad10)") (class "Default")
      (node (ref "U1") (pin "10") (pinfunction "PA15_10") (pintype "unspecified+no_connect"))
    )
    (net (code "60") (name "unconnected-(U1-PB3-Pad11)") (class "Default")
      (node (ref "U1") (pin "11") (pinfunction "PB3_11") (pintype "unspecified+no_connect"))
    )
    (net (code "61") (name "unconnected-(U1-PB4-Pad12)") (class "Default")
      (node (ref "U1") (pin "12") (pinfunction "PB4_12") (pintype "unspecified+no_connect"))
    )
    (net (code "62") (name "unconnected-(U1-PB5-Pad13)") (class "Default")
      (node (ref "U1") (pin "13") (pinfunction "PB5_13") (pintype "unspecified+no_connect"))
    )
    (net (code "63") (name "unconnected-(U1-PC13-Pad22)") (class "Default")
      (node (ref "U1") (pin "22") (pinfunction "PC13_22") (pintype "unspecified+no_connect"))
    )
    (net (code "64") (name "unconnected-(U1-PC14-Pad23)") (class "Default")
      (node (ref "U1") (pin "23") (pinfunction "PC14_23") (pintype "unspecified+no_connect"))
    )
    (net (code "65") (name "unconnected-(U1-PC15-Pad24)") (class "Default")
      (node (ref "U1") (pin "24") (pinfunction "PC15_24") (pintype "unspecified+no_connect"))
    )
    (net (code "66") (name "unconnected-(U1-VBAT-Pad21)") (class "Default")
      (node (ref "U1") (pin "21") (pinfunction "VBAT_21") (pintype "unspecified+no_connect"))
    )
    (net (code "67") (name "unconnected-(U2-NC-Pad3)") (class "Default")
      (node (ref "U2") (pin "3") (pinfunction "NC_3") (pintype "unspecified+no_connect"))
    )
  )
)
